# Adafruit_2_2in_TFT_HAT_rev_A.net
KiCad netlist of a schematic drawn in EAGLE
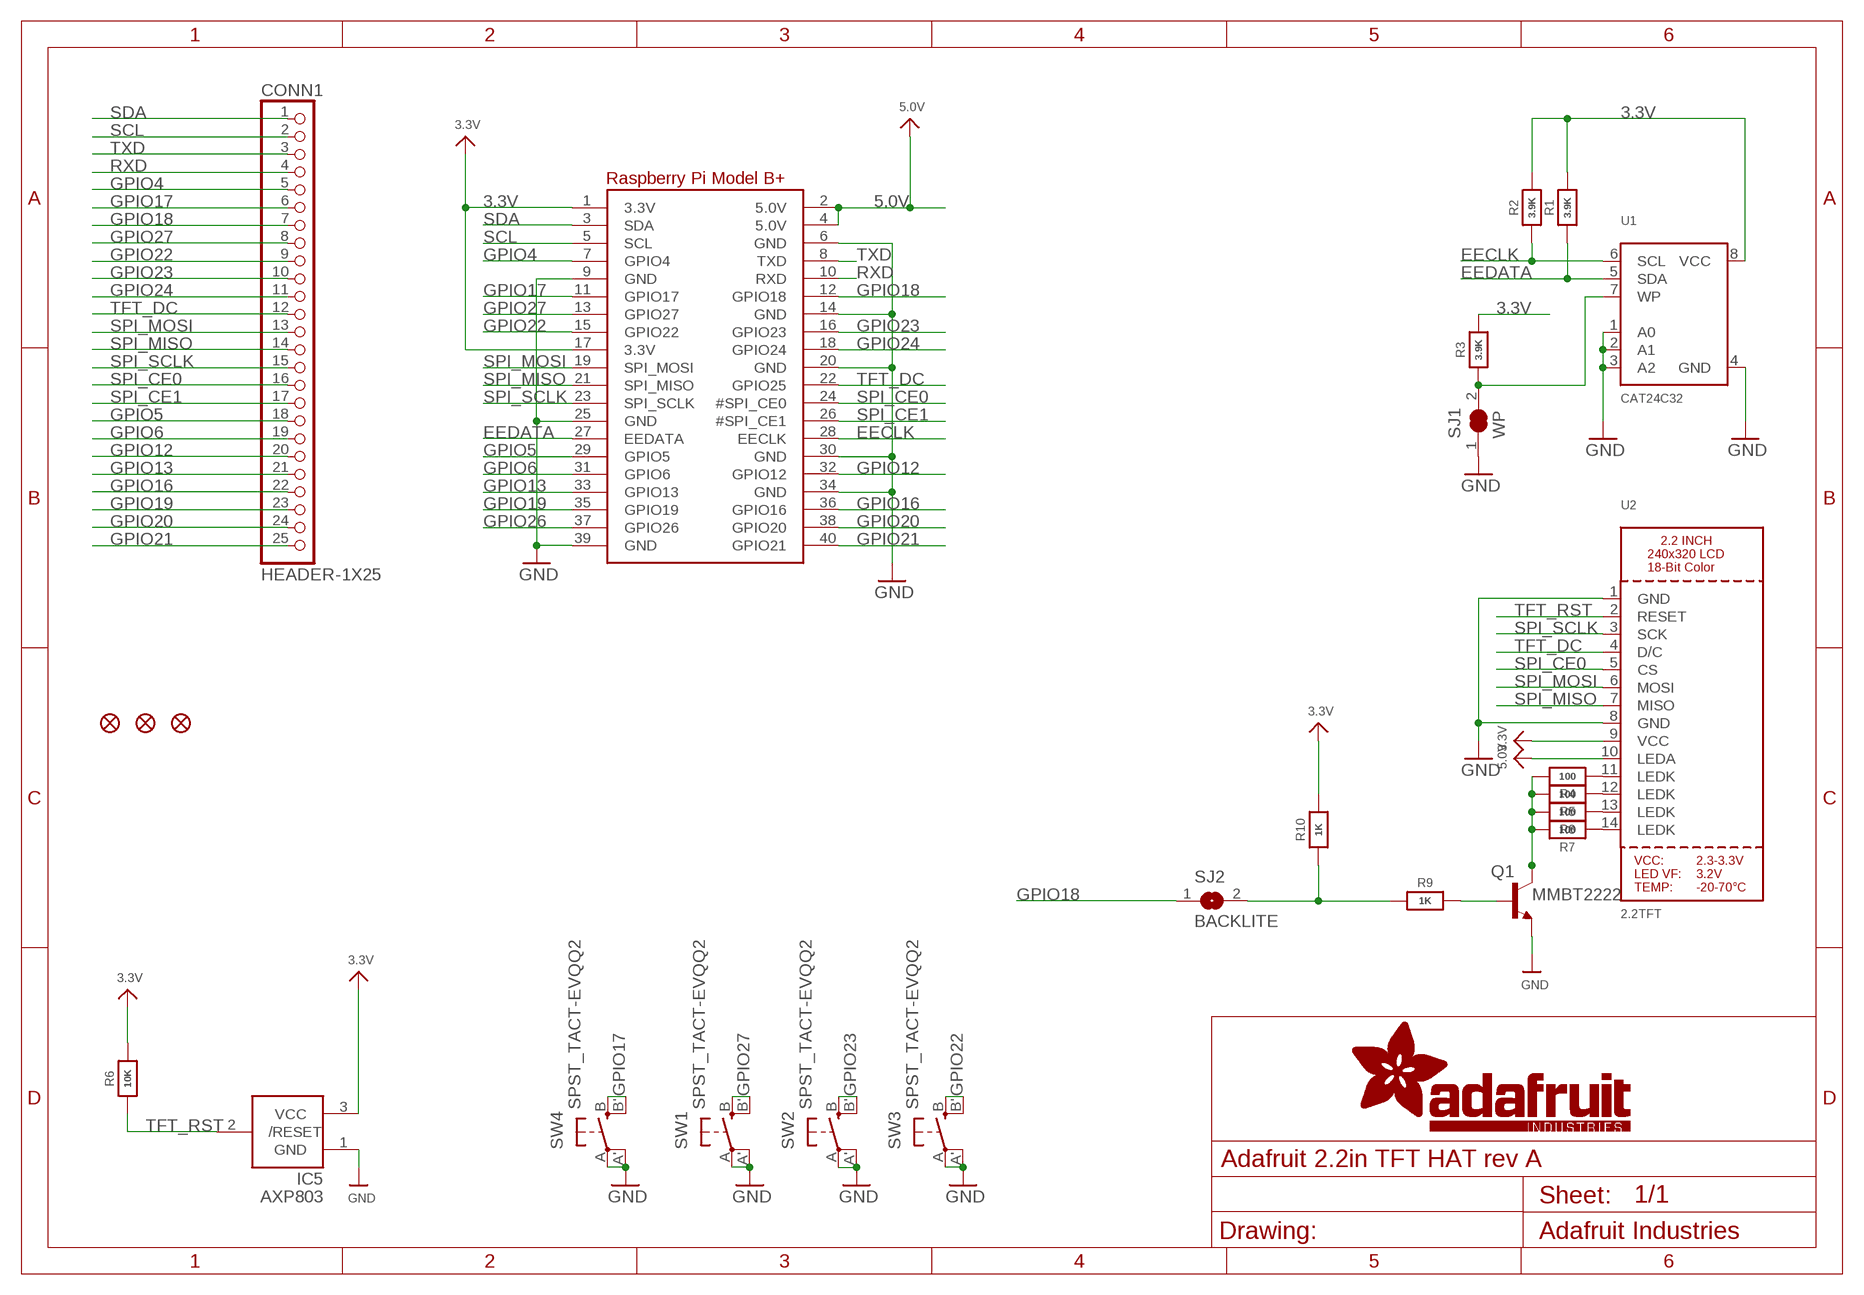
[diagram p0: schematic, sheet 1]

(export (version "E")
  (design (tool "Eeschema 10.0.6"))
  (components
    (comp (ref "CONN1")
      (value "HEADER-1X25")
      (footprint "eagle-import:1X25_ROUND_70MIL")
      (libsource (lib "eagle-import") (part "HEADER-1X25"))
    )
    (comp (ref "FID1")
      (value "FIDUCIAL\"\"")
      (footprint "eagle-import:FIDUCIAL_1MM")
      (libsource (lib "eagle-import") (part "FIDUCIAL{dblquote}{dblquote}"))
    )
    (comp (ref "FID2")
      (value "FIDUCIAL\"\"")
      (footprint "eagle-import:FIDUCIAL_1MM")
      (libsource (lib "eagle-import") (part "FIDUCIAL{dblquote}{dblquote}"))
    )
    (comp (ref "FID3")
      (value "FIDUCIAL\"\"")
      (footprint "eagle-import:FIDUCIAL_1MM")
      (libsource (lib "eagle-import") (part "FIDUCIAL{dblquote}{dblquote}"))
    )
    (comp (ref "IC5")
      (value "AXP803")
      (footprint "eagle-import:SOT23")
      (libsource (lib "eagle-import") (part "AXP083-SAG"))
    )
    (comp (ref "Q1")
      (value "MMBT2222")
      (footprint "eagle-import:SOT23-BEC")
      (libsource (lib "eagle-import") (part "-NPN-SOT23-BECMMBT2222ALT1"))
    )
    (comp (ref "R1")
      (value "3.9K")
      (footprint "eagle-import:0805-NO")
      (libsource (lib "eagle-import") (part "RESISTOR0805_NOOUTLINE"))
    )
    (comp (ref "R2")
      (value "3.9K")
      (footprint "eagle-import:0805-NO")
      (libsource (lib "eagle-import") (part "RESISTOR0805_NOOUTLINE"))
    )
    (comp (ref "R3")
      (value "3.9K")
      (footprint "eagle-import:0805-NO")
      (libsource (lib "eagle-import") (part "RESISTOR0805_NOOUTLINE"))
    )
    (comp (ref "R4")
      (value "100")
      (footprint "eagle-import:0805-NO")
      (libsource (lib "eagle-import") (part "RESISTOR0805_NOOUTLINE"))
    )
    (comp (ref "R5")
      (value "100")
      (footprint "eagle-import:0805-NO")
      (libsource (lib "eagle-import") (part "RESISTOR0805_NOOUTLINE"))
    )
    (comp (ref "R6")
      (value "10K")
      (footprint "eagle-import:0805-NO")
      (libsource (lib "eagle-import") (part "RESISTOR0805_NOOUTLINE"))
    )
    (comp (ref "R7")
      (value "100")
      (footprint "eagle-import:0805-NO")
      (libsource (lib "eagle-import") (part "RESISTOR0805_NOOUTLINE"))
    )
    (comp (ref "R8")
      (value "100")
      (footprint "eagle-import:0805-NO")
      (libsource (lib "eagle-import") (part "RESISTOR0805_NOOUTLINE"))
    )
    (comp (ref "R9")
      (value "1K")
      (footprint "eagle-import:0805-NO")
      (libsource (lib "eagle-import") (part "RESISTOR0805_NOOUTLINE"))
    )
    (comp (ref "R10")
      (value "1K")
      (footprint "eagle-import:0805-NO")
      (libsource (lib "eagle-import") (part "RESISTOR0805_NOOUTLINE"))
    )
    (comp (ref "RPI1")
      (value "RASPBERRYPI_BPLUS_HATNOSLOTS")
      (footprint "eagle-import:PI_HAT_NOSLOTS")
      (libsource (lib "eagle-import") (part "RASPBERRYPI_BPLUS_HATNOSLOTS"))
    )
    (comp (ref "SJ1")
      (value "WP")
      (footprint "eagle-import:SOLDERJUMPER_CLOSEDWIRE")
      (libsource (lib "eagle-import") (part "SOLDERJUMPER_CLOSED"))
    )
    (comp (ref "SJ2")
      (value "BACKLITE")
      (footprint "eagle-import:SOLDERJUMPER_CLOSEDWIRE")
      (libsource (lib "eagle-import") (part "SOLDERJUMPERCLOSED"))
    )
    (comp (ref "SW1")
      (value "SPST_TACT-EVQQ2")
      (footprint "eagle-import:EVQ-Q2")
      (libsource (lib "eagle-import") (part "SPST_TACT-EVQQ2"))
    )
    (comp (ref "SW2")
      (value "SPST_TACT-EVQQ2")
      (footprint "eagle-import:EVQ-Q2")
      (libsource (lib "eagle-import") (part "SPST_TACT-EVQQ2"))
    )
    (comp (ref "SW3")
      (value "SPST_TACT-EVQQ2")
      (footprint "eagle-import:EVQ-Q2")
      (libsource (lib "eagle-import") (part "SPST_TACT-EVQQ2"))
    )
    (comp (ref "SW4")
      (value "SPST_TACT-EVQQ2")
      (footprint "eagle-import:EVQ-Q2")
      (libsource (lib "eagle-import") (part "SPST_TACT-EVQQ2"))
    )
    (comp (ref "U1")
      (value "CAT24C32")
      (footprint "eagle-import:SOIC8_150MIL")
      (libsource (lib "eagle-import") (part "EEPROM_I2C_SOIC8_GENERIC"))
    )
    (comp (ref "U2")
      (value "2.2TFT")
      (footprint "eagle-import:TM022HDH26_2.2IN_LCD")
      (libsource (lib "eagle-import") (part "DISP_LCD_TM022HDH26"))
    )
  )
  (nets
    (net (code "1") (name "/EECLK") (class "Default")
      (node (ref "R2") (pin "1") (pinfunction "1_1") (pintype "passive"))
      (node (ref "RPI1") (pin "28") (pinfunction "EECLK_28") (pintype "power_in"))
      (node (ref "U1") (pin "6") (pinfunction "SCL_6") (pintype "input"))
    )
    (net (code "2") (name "/EEDATA") (class "Default")
      (node (ref "R1") (pin "1") (pinfunction "1_1") (pintype "passive"))
      (node (ref "RPI1") (pin "27") (pinfunction "EEDATA_27") (pintype "bidirectional"))
      (node (ref "U1") (pin "5") (pinfunction "SDA_5") (pintype "bidirectional"))
    )
    (net (code "3") (name "/GPIO4") (class "Default")
      (node (ref "CONN1") (pin "5") (pinfunction "5_5") (pintype "passive"))
      (node (ref "RPI1") (pin "7") (pinfunction "GPIO4_7") (pintype "bidirectional"))
    )
    (net (code "4") (name "/GPIO5") (class "Default")
      (node (ref "CONN1") (pin "18") (pinfunction "18_18") (pintype "passive"))
      (node (ref "RPI1") (pin "29") (pinfunction "GPIO5_29") (pintype "bidirectional"))
    )
    (net (code "5") (name "/GPIO6") (class "Default")
      (node (ref "CONN1") (pin "19") (pinfunction "19_19") (pintype "passive"))
      (node (ref "RPI1") (pin "31") (pinfunction "GPIO6_31") (pintype "power_in"))
    )
    (net (code "6") (name "/GPIO12") (class "Default")
      (node (ref "CONN1") (pin "20") (pinfunction "20_20") (pintype "passive"))
      (node (ref "RPI1") (pin "32") (pinfunction "GPIO12_32") (pintype "bidirectional"))
    )
    (net (code "7") (name "/GPIO13") (class "Default")
      (node (ref "CONN1") (pin "21") (pinfunction "21_21") (pintype "passive"))
      (node (ref "RPI1") (pin "33") (pinfunction "GPIO13_33") (pintype "bidirectional"))
    )
    (net (code "8") (name "/GPIO16") (class "Default")
      (node (ref "CONN1") (pin "22") (pinfunction "22_22") (pintype "passive"))
      (node (ref "RPI1") (pin "36") (pinfunction "GPIO16_36") (pintype "power_in"))
    )
    (net (code "9") (name "/GPIO17") (class "Default")
      (node (ref "CONN1") (pin "6") (pinfunction "6_6") (pintype "passive"))
      (node (ref "RPI1") (pin "11") (pinfunction "GPIO17_11") (pintype "bidirectional"))
      (node (ref "SW4") (pin "B") (pinfunction "S_B") (pintype "passive"))
      (node (ref "SW4") (pin "B'") (pinfunction "S1_B'") (pintype "passive"))
    )
    (net (code "10") (name "/GPIO18") (class "Default")
      (node (ref "CONN1") (pin "7") (pinfunction "7_7") (pintype "passive"))
      (node (ref "RPI1") (pin "12") (pinfunction "GPIO18_12") (pintype "bidirectional"))
      (node (ref "SJ2") (pin "1") (pinfunction "1_1") (pintype "passive"))
    )
    (net (code "11") (name "/GPIO19") (class "Default")
      (node (ref "CONN1") (pin "23") (pinfunction "23_23") (pintype "passive"))
      (node (ref "RPI1") (pin "35") (pinfunction "GPIO19_35") (pintype "bidirectional"))
    )
    (net (code "12") (name "/GPIO20") (class "Default")
      (node (ref "CONN1") (pin "24") (pinfunction "24_24") (pintype "passive"))
      (node (ref "RPI1") (pin "38") (pinfunction "GPIO20_38") (pintype "bidirectional"))
    )
    (net (code "13") (name "/GPIO21") (class "Default")
      (node (ref "CONN1") (pin "25") (pinfunction "25_25") (pintype "passive"))
      (node (ref "RPI1") (pin "40") (pinfunction "GPIO21_40") (pintype "bidirectional"))
    )
    (net (code "14") (name "/GPIO22") (class "Default")
      (node (ref "CONN1") (pin "9") (pinfunction "9_9") (pintype "passive"))
      (node (ref "RPI1") (pin "15") (pinfunction "GPIO22_15") (pintype "bidirectional"))
      (node (ref "SW3") (pin "B") (pinfunction "S_B") (pintype "passive"))
      (node (ref "SW3") (pin "B'") (pinfunction "S1_B'") (pintype "passive"))
    )
    (net (code "15") (name "/GPIO23") (class "Default")
      (node (ref "CONN1") (pin "10") (pinfunction "10_10") (pintype "passive"))
      (node (ref "RPI1") (pin "16") (pinfunction "GPIO23_16") (pintype "bidirectional"))
      (node (ref "SW2") (pin "B") (pinfunction "S_B") (pintype "passive"))
      (node (ref "SW2") (pin "B'") (pinfunction "S1_B'") (pintype "passive"))
    )
    (net (code "16") (name "/GPIO24") (class "Default")
      (node (ref "CONN1") (pin "11") (pinfunction "11_11") (pintype "passive"))
      (node (ref "RPI1") (pin "18") (pinfunction "GPIO24_18") (pintype "bidirectional"))
    )
    (net (code "17") (name "/GPIO26") (class "Default")
      (node (ref "RPI1") (pin "37") (pinfunction "GPIO26_37") (pintype "bidirectional"))
    )
    (net (code "18") (name "/GPIO27") (class "Default")
      (node (ref "CONN1") (pin "8") (pinfunction "8_8") (pintype "passive"))
      (node (ref "RPI1") (pin "13") (pinfunction "GPIO27_13") (pintype "bidirectional"))
      (node (ref "SW1") (pin "B") (pinfunction "S_B") (pintype "passive"))
      (node (ref "SW1") (pin "B'") (pinfunction "S1_B'") (pintype "passive"))
    )
    (net (code "19") (name "/RXD") (class "Default")
      (node (ref "CONN1") (pin "4") (pinfunction "4_4") (pintype "passive"))
      (node (ref "RPI1") (pin "10") (pinfunction "RXD_10") (pintype "bidirectional"))
    )
    (net (code "20") (name "/SCL") (class "Default")
      (node (ref "CONN1") (pin "2") (pinfunction "2_2") (pintype "passive"))
      (node (ref "RPI1") (pin "5") (pinfunction "SCL_5") (pintype "bidirectional"))
    )
    (net (code "21") (name "/SDA") (class "Default")
      (node (ref "CONN1") (pin "1") (pinfunction "1_1") (pintype "passive"))
      (node (ref "RPI1") (pin "3") (pinfunction "SDA_3") (pintype "bidirectional"))
    )
    (net (code "22") (name "/SPI_CE0") (class "Default")
      (node (ref "CONN1") (pin "16") (pinfunction "16_16") (pintype "passive"))
      (node (ref "RPI1") (pin "24") (pinfunction "#SPI_CE0_24") (pintype "bidirectional"))
      (node (ref "U2") (pin "5") (pinfunction "CS_5") (pintype "input"))
    )
    (net (code "23") (name "/SPI_CE1") (class "Default")
      (node (ref "CONN1") (pin "17") (pinfunction "17_17") (pintype "passive"))
      (node (ref "RPI1") (pin "26") (pinfunction "#SPI_CE1_26") (pintype "bidirectional"))
    )
    (net (code "24") (name "/SPI_MISO") (class "Default")
      (node (ref "CONN1") (pin "14") (pinfunction "14_14") (pintype "passive"))
      (node (ref "RPI1") (pin "21") (pinfunction "SPI_MISO_21") (pintype "bidirectional"))
      (node (ref "U2") (pin "7") (pinfunction "MISO_7") (pintype "output"))
    )
    (net (code "25") (name "/SPI_MOSI") (class "Default")
      (node (ref "CONN1") (pin "13") (pinfunction "13_13") (pintype "passive"))
      (node (ref "RPI1") (pin "19") (pinfunction "SPI_MOSI_19") (pintype "bidirectional"))
      (node (ref "U2") (pin "6") (pinfunction "MOSI_6") (pintype "input"))
    )
    (net (code "26") (name "/SPI_SCLK") (class "Default")
      (node (ref "CONN1") (pin "15") (pinfunction "15_15") (pintype "passive"))
      (node (ref "RPI1") (pin "23") (pinfunction "SPI_SCLK_23") (pintype "bidirectional"))
      (node (ref "U2") (pin "3") (pinfunction "SCK_3") (pintype "input"))
    )
    (net (code "27") (name "/TFT_DC") (class "Default")
      (node (ref "CONN1") (pin "12") (pinfunction "12_12") (pintype "passive"))
      (node (ref "RPI1") (pin "22") (pinfunction "GPIO25_22") (pintype "bidirectional"))
      (node (ref "U2") (pin "4") (pinfunction "D/C_4") (pintype "input"))
    )
    (net (code "28") (name "/TFT_RST") (class "Default")
      (node (ref "IC5") (pin "2") (pinfunction "/RESET_2") (pintype "output"))
      (node (ref "R6") (pin "1") (pinfunction "1_1") (pintype "passive"))
      (node (ref "U2") (pin "2") (pinfunction "RESET_2") (pintype "input"))
    )
    (net (code "29") (name "/TXD") (class "Default")
      (node (ref "CONN1") (pin "3") (pinfunction "3_3") (pintype "passive"))
      (node (ref "RPI1") (pin "8") (pinfunction "TXD_8") (pintype "output"))
    )
    (net (code "30") (name "3.3V") (class "Default")
      (node (ref "IC5") (pin "3") (pinfunction "VCC_3") (pintype "power_in"))
      (node (ref "R1") (pin "2") (pinfunction "2_2") (pintype "passive"))
      (node (ref "R10") (pin "2") (pinfunction "2_2") (pintype "passive"))
      (node (ref "R2") (pin "2") (pinfunction "2_2") (pintype "passive"))
      (node (ref "R3") (pin "2") (pinfunction "2_2") (pintype "passive"))
      (node (ref "R6") (pin "2") (pinfunction "2_2") (pintype "passive"))
      (node (ref "RPI1") (pin "1") (pinfunction "3.3V_1") (pintype "power_in"))
      (node (ref "RPI1") (pin "17") (pinfunction "3.3V_17") (pintype "power_in"))
      (node (ref "U1") (pin "8") (pinfunction "VCC_8") (pintype "power_in"))
      (node (ref "U2") (pin "9") (pinfunction "VCC_9") (pintype "power_in"))
    )
    (net (code "31") (name "5.0V") (class "Default")
      (node (ref "RPI1") (pin "2") (pinfunction "5.0V_2") (pintype "power_in"))
      (node (ref "RPI1") (pin "4") (pinfunction "5.0V_4") (pintype "power_in"))
      (node (ref "U2") (pin "10") (pinfunction "LEDA_10") (pintype "power_in"))
    )
    (net (code "32") (name "GND") (class "Default")
      (node (ref "IC5") (pin "1") (pinfunction "GND_1") (pintype "power_in"))
      (node (ref "Q1") (pin "E") (pinfunction "E_E") (pintype "passive"))
      (node (ref "RPI1") (pin "14") (pinfunction "GND_14") (pintype "power_in"))
      (node (ref "RPI1") (pin "20") (pinfunction "GND_20") (pintype "power_in"))
      (node (ref "RPI1") (pin "25") (pinfunction "GND_25") (pintype "power_in"))
      (node (ref "RPI1") (pin "30") (pinfunction "GND_30") (pintype "bidirectional"))
      (node (ref "RPI1") (pin "34") (pinfunction "GND_34") (pintype "bidirectional"))
      (node (ref "RPI1") (pin "39") (pinfunction "GND_39") (pintype "power_in"))
      (node (ref "RPI1") (pin "6") (pinfunction "GND_6") (pintype "power_in"))
      (node (ref "RPI1") (pin "9") (pinfunction "GND_9") (pintype "power_in"))
      (node (ref "SJ1") (pin "1") (pinfunction "1_1") (pintype "passive"))
      (node (ref "SW1") (pin "A") (pinfunction "P_A") (pintype "passive"))
      (node (ref "SW1") (pin "A'") (pinfunction "P1_A'") (pintype "passive"))
      (node (ref "SW2") (pin "A") (pinfunction "P_A") (pintype "passive"))
      (node (ref "SW2") (pin "A'") (pinfunction "P1_A'") (pintype "passive"))
      (node (ref "SW3") (pin "A") (pinfunction "P_A") (pintype "passive"))
      (node (ref "SW3") (pin "A'") (pinfunction "P1_A'") (pintype "passive"))
      (node (ref "SW4") (pin "A") (pinfunction "P_A") (pintype "passive"))
      (node (ref "SW4") (pin "A'") (pinfunction "P1_A'") (pintype "passive"))
      (node (ref "U1") (pin "1") (pinfunction "A0_1") (pintype "input"))
      (node (ref "U1") (pin "2") (pinfunction "A1_2") (pintype "input"))
      (node (ref "U1") (pin "3") (pinfunction "A2_3") (pintype "input"))
      (node (ref "U1") (pin "4") (pinfunction "GND_4") (pintype "power_in"))
      (node (ref "U2") (pin "1") (pinfunction "GND_1") (pintype "power_in"))
      (node (ref "U2") (pin "8") (pinfunction "GND_8") (pintype "power_in"))
    )
    (net (code "33") (name "Net-(Q1-PadB)") (class "Default")
      (node (ref "Q1") (pin "B") (pinfunction "B_B") (pintype "passive"))
      (node (ref "R9") (pin "2") (pinfunction "2_2") (pintype "passive"))
    )
    (net (code "34") (name "Net-(Q1-PadC)") (class "Default")
      (node (ref "Q1") (pin "C") (pinfunction "C_C") (pintype "passive"))
      (node (ref "R4") (pin "2") (pinfunction "2_2") (pintype "passive"))
      (node (ref "R5") (pin "2") (pinfunction "2_2") (pintype "passive"))
      (node (ref "R7") (pin "2") (pinfunction "2_2") (pintype "passive"))
      (node (ref "R8") (pin "2") (pinfunction "2_2") (pintype "passive"))
    )
    (net (code "35") (name "Net-(R4-Pad1)") (class "Default")
      (node (ref "R4") (pin "1") (pinfunction "1_1") (pintype "passive"))
      (node (ref "U2") (pin "11") (pinfunction "LEDK_11") (pintype "power_in"))
    )
    (net (code "36") (name "Net-(R5-Pad1)") (class "Default")
      (node (ref "R5") (pin "1") (pinfunction "1_1") (pintype "passive"))
      (node (ref "U2") (pin "12") (pinfunction "LEDK_12") (pintype "power_in"))
    )
    (net (code "37") (name "Net-(R7-Pad1)") (class "Default")
      (node (ref "R7") (pin "1") (pinfunction "1_1") (pintype "passive"))
      (node (ref "U2") (pin "14") (pinfunction "LEDK_14") (pintype "power_in"))
    )
    (net (code "38") (name "Net-(R8-Pad1)") (class "Default")
      (node (ref "R8") (pin "1") (pinfunction "1_1") (pintype "passive"))
      (node (ref "U2") (pin "13") (pinfunction "LEDK_13") (pintype "power_in"))
    )
    (net (code "39") (name "Net-(R10-Pad1)") (class "Default")
      (node (ref "R10") (pin "1") (pinfunction "1_1") (pintype "passive"))
      (node (ref "R9") (pin "1") (pinfunction "1_1") (pintype "passive"))
      (node (ref "SJ2") (pin "2") (pinfunction "2_2") (pintype "passive"))
    )
    (net (code "40") (name "Net-(U1-WP)") (class "Default")
      (node (ref "R3") (pin "1") (pinfunction "1_1") (pintype "passive"))
      (node (ref "SJ1") (pin "2") (pinfunction "2_2") (pintype "passive"))
      (node (ref "U1") (pin "7") (pinfunction "WP_7") (pintype "input"))
    )
  )
)
